# 4-KEY-KEYBOARD.net
KiCad netlist of a schematic drawn in EAGLE
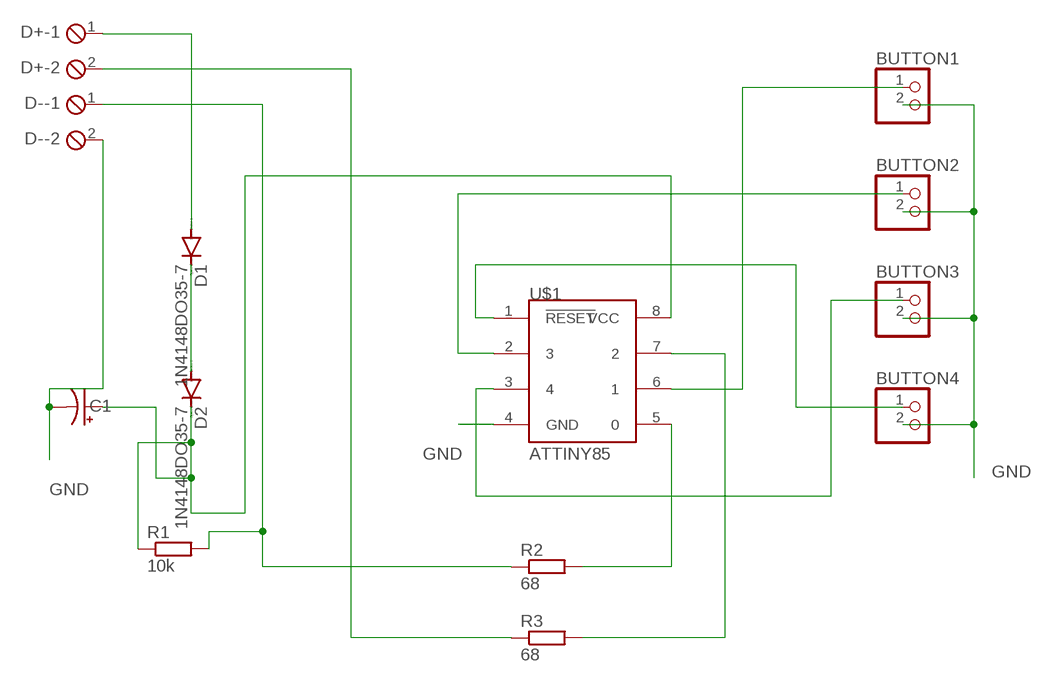
[diagram p0: schematic, sheet 1]

(export (version "E")
  (design (tool "Eeschema 10.0.6"))
  (components
    (comp (ref "BUTTON1")
      (value "PINHD-1X2")
      (footprint "eagle-import:1X02")
      (libsource (lib "eagle-import") (part "PINHD-1X2"))
    )
    (comp (ref "BUTTON2")
      (value "PINHD-1X2")
      (footprint "eagle-import:1X02")
      (libsource (lib "eagle-import") (part "PINHD-1X2"))
    )
    (comp (ref "BUTTON3")
      (value "PINHD-1X2")
      (footprint "eagle-import:1X02")
      (libsource (lib "eagle-import") (part "PINHD-1X2"))
    )
    (comp (ref "BUTTON4")
      (value "PINHD-1X2")
      (footprint "eagle-import:1X02")
      (libsource (lib "eagle-import") (part "PINHD-1X2"))
    )
    (comp (ref "C1")
      (value "CPOL-USE2.5-6")
      (footprint "eagle-import:E2,5-6")
      (libsource (lib "eagle-import") (part "CPOL-USE2.5-6"))
    )
    (comp (ref "D+")
      (value "MPT2")
      (footprint "eagle-import:2POL254")
      (libsource (lib "eagle-import") (part "MPT2"))
    )
    (comp (ref "D-")
      (value "MPT2")
      (footprint "eagle-import:2POL254")
      (libsource (lib "eagle-import") (part "MPT2"))
    )
    (comp (ref "D1")
      (value "1N4148DO35-7")
      (footprint "eagle-import:DO35-7")
      (libsource (lib "eagle-import") (part "1N4148DO35-7"))
    )
    (comp (ref "D2")
      (value "1N4148DO35-7")
      (footprint "eagle-import:DO35-7")
      (libsource (lib "eagle-import") (part "1N4148DO35-7"))
    )
    (comp (ref "R1")
      (value "10k")
      (footprint "eagle-import:0204_7")
      (libsource (lib "eagle-import") (part "R-EU_0204/7"))
    )
    (comp (ref "R2")
      (value "68")
      (footprint "eagle-import:0204_7")
      (libsource (lib "eagle-import") (part "R-EU_0204/7"))
    )
    (comp (ref "R3")
      (value "68")
      (footprint "eagle-import:0204_7")
      (libsource (lib "eagle-import") (part "R-EU_0204/7"))
    )
    (comp (ref "U$1")
      (value "ATTINY85")
      (footprint "eagle-import:8P3")
      (libsource (lib "eagle-import") (part "ATTINY85"))
    )
  )
  (nets
    (net (code "1") (name "/GND") (class "Default")
      (node (ref "BUTTON1") (pin "2") (pinfunction "2_2") (pintype "passive"))
      (node (ref "BUTTON2") (pin "2") (pinfunction "2_2") (pintype "passive"))
      (node (ref "BUTTON3") (pin "2") (pinfunction "2_2") (pintype "passive"))
      (node (ref "BUTTON4") (pin "2") (pinfunction "2_2") (pintype "passive"))
      (node (ref "C1") (pin "-") (pinfunction "-_-") (pintype "passive"))
      (node (ref "D-") (pin "2") (pinfunction "1_2") (pintype "passive"))
      (node (ref "U$1") (pin "4") (pinfunction "GND_4") (pintype "power_in"))
    )
    (net (code "2") (name "Net-(D+-Pad1)") (class "Default")
      (node (ref "D+") (pin "1") (pinfunction "1_1") (pintype "passive"))
      (node (ref "D1") (pin "A") (pinfunction "A_A") (pintype "passive"))
    )
    (net (code "3") (name "Net-(D+B-1)") (class "Default")
      (node (ref "D+") (pin "2") (pinfunction "1_2") (pintype "passive"))
      (node (ref "R3") (pin "1") (pinfunction "1_1") (pintype "passive"))
    )
    (net (code "4") (name "Net-(D--Pad1)") (class "Default")
      (node (ref "D-") (pin "1") (pinfunction "1_1") (pintype "passive"))
      (node (ref "R1") (pin "2") (pinfunction "2_2") (pintype "passive"))
      (node (ref "R2") (pin "1") (pinfunction "1_1") (pintype "passive"))
    )
    (net (code "5") (name "Net-(D1-PadC)") (class "Default")
      (node (ref "D1") (pin "C") (pinfunction "C_C") (pintype "passive"))
      (node (ref "D2") (pin "A") (pinfunction "A_A") (pintype "passive"))
    )
    (net (code "6") (name "Net-(U$1-0)") (class "Default")
      (node (ref "R2") (pin "2") (pinfunction "2_2") (pintype "passive"))
      (node (ref "U$1") (pin "5") (pinfunction "0_5") (pintype "bidirectional"))
    )
    (net (code "7") (name "Net-(U$1-1)") (class "Default")
      (node (ref "BUTTON1") (pin "1") (pinfunction "1_1") (pintype "passive"))
      (node (ref "U$1") (pin "6") (pinfunction "1_6") (pintype "bidirectional"))
    )
    (net (code "8") (name "Net-(U$1-2)") (class "Default")
      (node (ref "R3") (pin "2") (pinfunction "2_2") (pintype "passive"))
      (node (ref "U$1") (pin "7") (pinfunction "2_7") (pintype "bidirectional"))
    )
    (net (code "9") (name "Net-(U$1-3)") (class "Default")
      (node (ref "BUTTON2") (pin "1") (pinfunction "1_1") (pintype "passive"))
      (node (ref "U$1") (pin "2") (pinfunction "3_2") (pintype "bidirectional"))
    )
    (net (code "10") (name "Net-(U$1-4)") (class "Default")
      (node (ref "BUTTON3") (pin "1") (pinfunction "1_1") (pintype "passive"))
      (node (ref "U$1") (pin "3") (pinfunction "4_3") (pintype "bidirectional"))
    )
    (net (code "11") (name "Net-(U$1-VCC)") (class "Default")
      (node (ref "C1") (pin "+") (pinfunction "+_+") (pintype "passive"))
      (node (ref "D2") (pin "C") (pinfunction "C_C") (pintype "passive"))
      (node (ref "R1") (pin "1") (pinfunction "1_1") (pintype "passive"))
      (node (ref "U$1") (pin "8") (pinfunction "VCC_8") (pintype "power_in"))
    )
    (net (code "12") (name "Net-(U$1-~{RESET})") (class "Default")
      (node (ref "BUTTON4") (pin "1") (pinfunction "1_1") (pintype "passive"))
      (node (ref "U$1") (pin "1") (pinfunction "~{RESET}_1") (pintype "bidirectional"))
    )
  )
)
